# zigduino-v6d.net
KiCad netlist of a schematic drawn in EAGLE
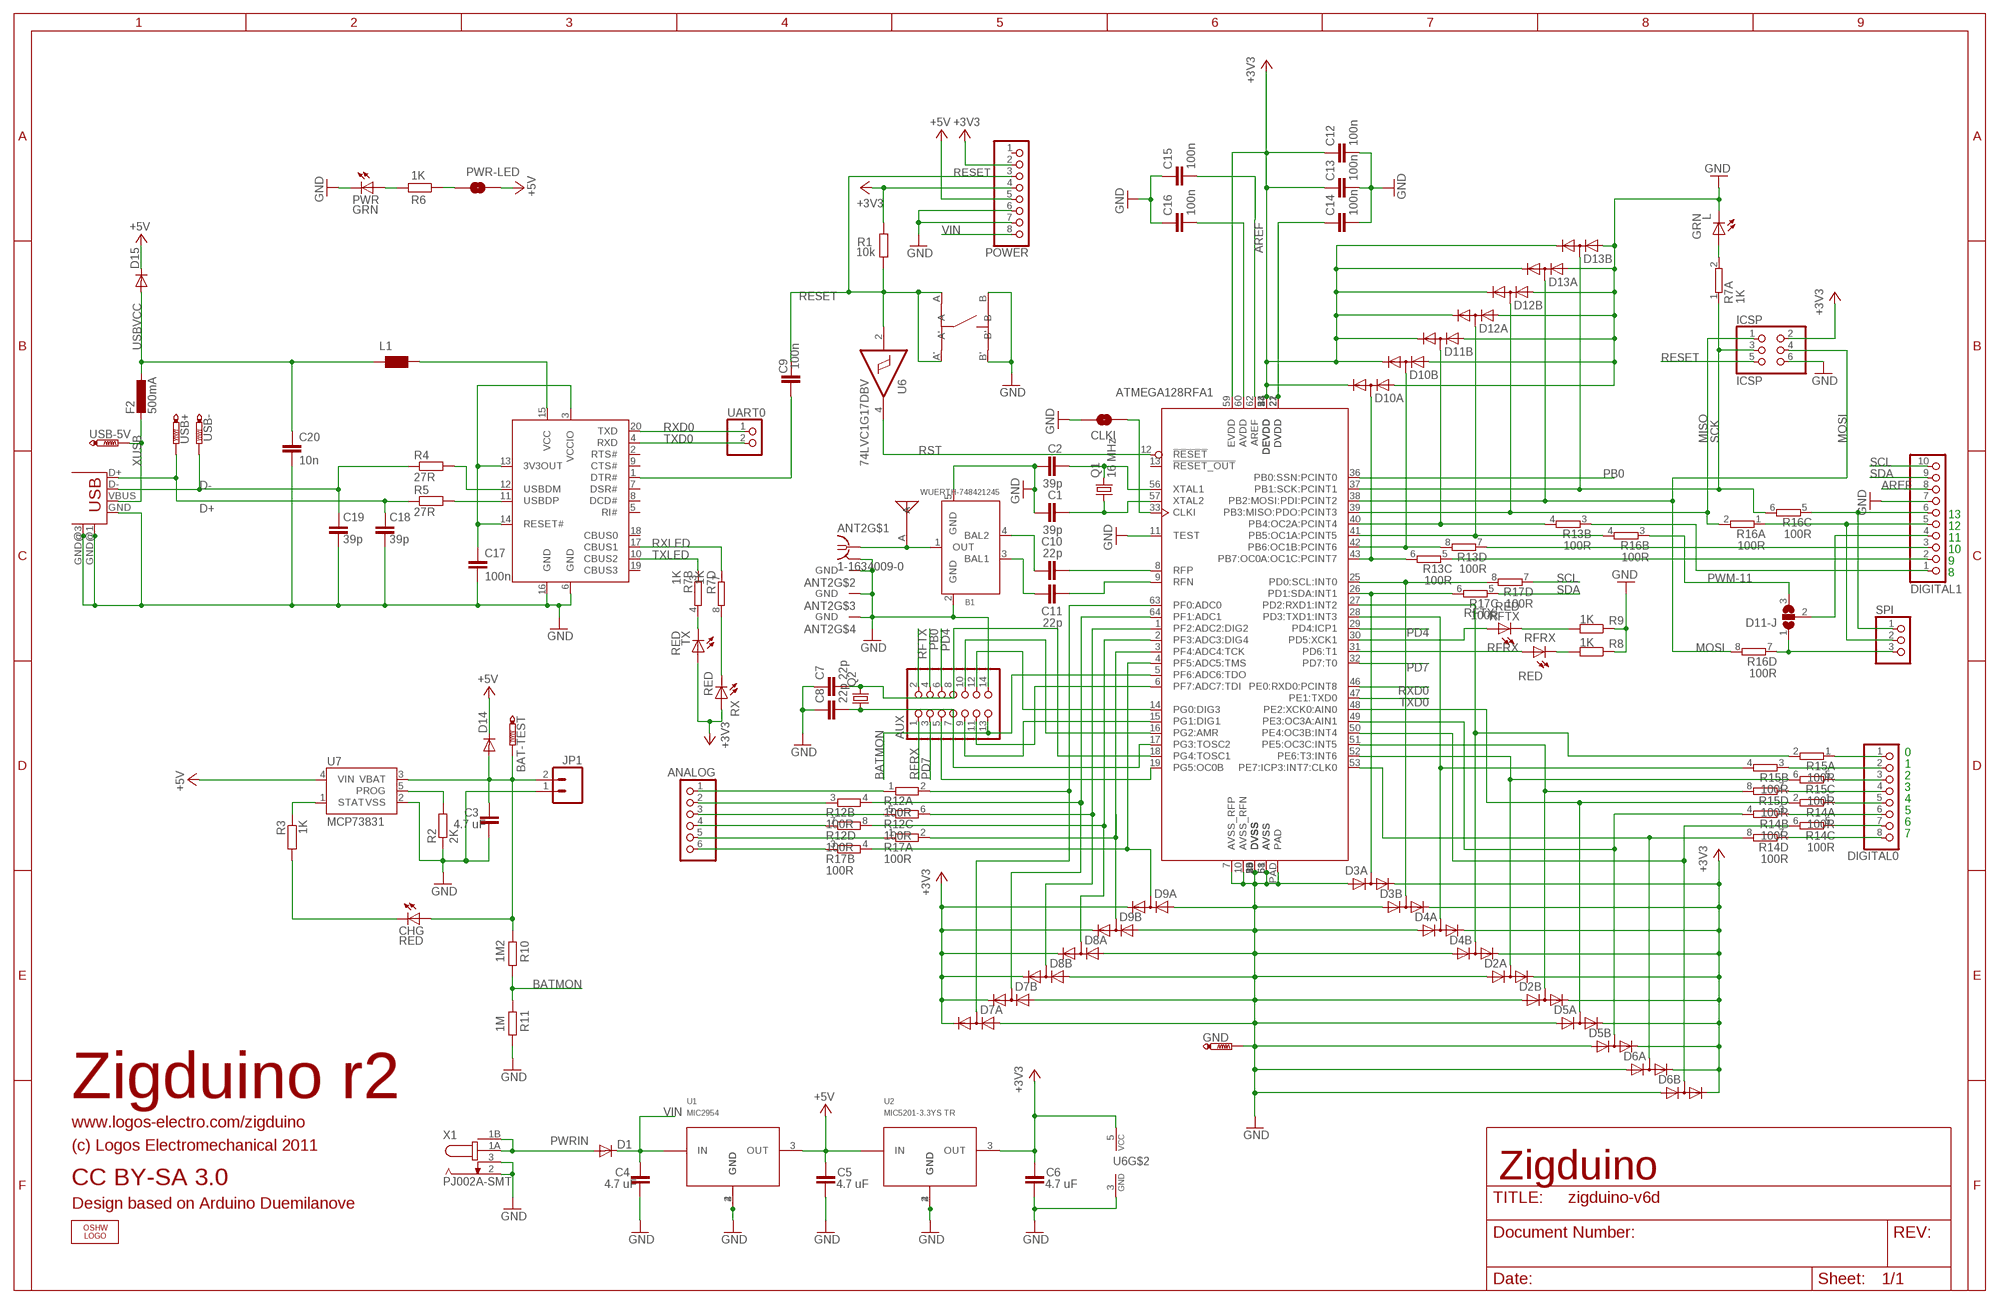
[diagram p0: schematic, sheet 1]

(export (version "E")
  (design (tool "Eeschema 10.0.6"))
  (components
    (comp (ref "ANALOG")
      (value "PINHD-1X6")
      (footprint "eagle-import:1X06")
      (fields (field (name "PARTNO") "19742"))
      (libsource (lib "eagle-import") (part "PINHD-1X6"))
    )
    (comp (ref "ANT1")
      (value "MOLEX-ANT")
      (footprint "eagle-import:MOLEX-ANT")
      (fields (field (name "PARTNO") "0479480001"))
      (libsource (lib "eagle-import") (part "MOLEX-ANT"))
    )
    (comp (ref "ANT2")
      (value "1-1634009-0")
      (footprint "eagle-import:MMCX-THRU")
      (fields (field (name "BOM") "EXCLUDE") (field (name "DNP") "T"))
      (libsource (lib "eagle-import") (part "1-1634009-0"))
    )
    (comp (ref "AUX")
      (value "PINHD-2X7_2.00")
      (footprint "eagle-import:2X07M")
      (fields (field (name "PARTNO") "00217"))
      (libsource (lib "eagle-import") (part "PINHD-2X7_2.00"))
    )
    (comp (ref "B1")
      (value "WUERTH-748421245")
      (footprint "eagle-import:WURTH-BALUN")
      (fields (field (name "PARTNO") "748421245"))
      (libsource (lib "eagle-import") (part "WUERTH-748421245"))
    )
    (comp (ref "BAT-TEST")
      (value "PTR1TP13SQ")
      (footprint "eagle-import:TP13SQ")
      (fields (field (name "PARTNO") "TP13"))
      (libsource (lib "eagle-import") (part "PTR1TP13SQ"))
    )
    (comp (ref "C1")
      (value "39p")
      (footprint "eagle-import:C0603")
      (fields (field (name "PARTNO") "C1608C0G1H390J"))
      (libsource (lib "eagle-import") (part "C-EUC0603"))
    )
    (comp (ref "C2")
      (value "39p")
      (footprint "eagle-import:C0603")
      (fields (field (name "PARTNO") "C1608C0G1H390J"))
      (libsource (lib "eagle-import") (part "C-EUC0603"))
    )
    (comp (ref "C3")
      (value "4.7 uF")
      (footprint "eagle-import:C1206")
      (fields (field (name "PARTNO") "C3216Y5V1H475Z"))
      (libsource (lib "eagle-import") (part "C-EUC1206"))
    )
    (comp (ref "C4")
      (value "4.7 uF")
      (footprint "eagle-import:C1206")
      (fields (field (name "PARTNO") "C3216Y5V1H475Z"))
      (libsource (lib "eagle-import") (part "C-EUC1206"))
    )
    (comp (ref "C5")
      (value "4.7 uF")
      (footprint "eagle-import:C1206")
      (fields (field (name "PARTNO") "C3216Y5V1H475Z"))
      (libsource (lib "eagle-import") (part "C-EUC1206"))
    )
    (comp (ref "C6")
      (value "4.7 uF")
      (footprint "eagle-import:C1206")
      (fields (field (name "PARTNO") "C3216Y5V1H475Z"))
      (libsource (lib "eagle-import") (part "C-EUC1206"))
    )
    (comp (ref "C7")
      (value "22p")
      (footprint "eagle-import:C0603")
      (fields (field (name "PARTNO") "GQM1885C1H220JB01D"))
      (libsource (lib "eagle-import") (part "C-EUC0603"))
    )
    (comp (ref "C8")
      (value "22p")
      (footprint "eagle-import:C0603")
      (fields (field (name "PARTNO") "GQM1885C1H220JB01D"))
      (libsource (lib "eagle-import") (part "C-EUC0603"))
    )
    (comp (ref "C9")
      (value "100n")
      (footprint "eagle-import:C0603")
      (fields (field (name "PARTNO") "CC0603MRY5V9BB104"))
      (libsource (lib "eagle-import") (part "C-EUC0603"))
    )
    (comp (ref "C10")
      (value "22p")
      (footprint "eagle-import:C0603")
      (fields (field (name "PARTNO") "GQM1885C1H220JB01D"))
      (libsource (lib "eagle-import") (part "C-EUC0603"))
    )
    (comp (ref "C11")
      (value "22p")
      (footprint "eagle-import:C0603")
      (fields (field (name "PARTNO") "GQM1885C1H220JB01D"))
      (libsource (lib "eagle-import") (part "C-EUC0603"))
    )
    (comp (ref "C12")
      (value "100n")
      (footprint "eagle-import:C0603")
      (fields (field (name "PARTNO") "CC0603MRY5V9BB104"))
      (libsource (lib "eagle-import") (part "C-EUC0603"))
    )
    (comp (ref "C13")
      (value "100n")
      (footprint "eagle-import:C0603")
      (fields (field (name "PARTNO") "CC0603MRY5V9BB104"))
      (libsource (lib "eagle-import") (part "C-EUC0603"))
    )
    (comp (ref "C14")
      (value "100n")
      (footprint "eagle-import:C0603")
      (fields (field (name "PARTNO") "CC0603MRY5V9BB104"))
      (libsource (lib "eagle-import") (part "C-EUC0603"))
    )
    (comp (ref "C15")
      (value "100n")
      (footprint "eagle-import:C0603")
      (fields (field (name "PARTNO") "CC0603MRY5V9BB104"))
      (libsource (lib "eagle-import") (part "C-EUC0603"))
    )
    (comp (ref "C16")
      (value "100n")
      (footprint "eagle-import:C0603")
      (fields (field (name "PARTNO") "CC0603MRY5V9BB104"))
      (libsource (lib "eagle-import") (part "C-EUC0603"))
    )
    (comp (ref "C17")
      (value "100n")
      (footprint "eagle-import:C0603")
      (fields (field (name "PARTNO") "CC0603MRY5V9BB104"))
      (libsource (lib "eagle-import") (part "C-EUC0603"))
    )
    (comp (ref "C18")
      (value "39p")
      (footprint "eagle-import:C0603")
      (fields (field (name "PARTNO") "C1608C0G1H390J"))
      (libsource (lib "eagle-import") (part "C-EUC0603"))
    )
    (comp (ref "C19")
      (value "39p")
      (footprint "eagle-import:C0603")
      (fields (field (name "PARTNO") "C1608C0G1H390J"))
      (libsource (lib "eagle-import") (part "C-EUC0603"))
    )
    (comp (ref "C20")
      (value "10n")
      (footprint "eagle-import:C0603")
      (fields (field (name "PARTNO") "GRM188R71H103KA01D"))
      (libsource (lib "eagle-import") (part "C-EUC0603"))
    )
    (comp (ref "CHG")
      (value "RED")
      (footprint "eagle-import:CHIP-LED0603")
      (fields (field (name "PARTNO") "LTST-C193KRKT-5A"))
      (libsource (lib "eagle-import") (part "LEDCHIP-LED0603"))
    )
    (comp (ref "CLKI")
      (value "SOLDERJUMPERTRACE")
      (footprint "eagle-import:SJ_2S-TRACE")
      (libsource (lib "eagle-import") (part "SOLDERJUMPERTRACE"))
    )
    (comp (ref "D1")
      (value "DIODE-SMB")
      (footprint "eagle-import:SMB")
      (fields (field (name "PARTNO") "B150B-13-F"))
      (libsource (lib "eagle-import") (part "DIODE-SMB"))
    )
    (comp (ref "D2")
      (value "SD103ASDM")
      (footprint "eagle-import:SOT26")
      (fields
        (field (name "BOM") "INCLUDE")
        (field (name "PARTNO") "SD103ASDM-7")
        (field (name "VOLT") "40V")
      )
      (libsource (lib "eagle-import") (part "SD103ASDM"))
    )
    (comp (ref "D3")
      (value "SD103ASDM")
      (footprint "eagle-import:SOT26")
      (fields
        (field (name "PARTNO") "SD103ASDM-7")
        (field (name "BOM") "INCLUDE")
        (field (name "VOLT") "40V")
      )
      (libsource (lib "eagle-import") (part "SD103ASDM"))
    )
    (comp (ref "D4")
      (value "SD103ASDM")
      (footprint "eagle-import:SOT26")
      (fields
        (field (name "PARTNO") "SD103ASDM-7")
        (field (name "VOLT") "40V")
        (field (name "BOM") "INCLUDE")
      )
      (libsource (lib "eagle-import") (part "SD103ASDM"))
    )
    (comp (ref "D5")
      (value "SD103ASDM")
      (footprint "eagle-import:SOT26")
      (fields
        (field (name "PARTNO") "SD103ASDM-7")
        (field (name "VOLT") "40V")
        (field (name "BOM") "INCLUDE")
      )
      (libsource (lib "eagle-import") (part "SD103ASDM"))
    )
    (comp (ref "D6")
      (value "SD103ASDM")
      (footprint "eagle-import:SOT26")
      (fields
        (field (name "PARTNO") "SD103ASDM-7")
        (field (name "VOLT") "40V")
        (field (name "BOM") "INCLUDE")
      )
      (libsource (lib "eagle-import") (part "SD103ASDM"))
    )
    (comp (ref "D7")
      (value "SD103ASDM")
      (footprint "eagle-import:SOT26")
      (fields
        (field (name "BOM") "INCLUDE")
        (field (name "PARTNO") "SD103ASDM-7")
        (field (name "VOLT") "40V")
      )
      (libsource (lib "eagle-import") (part "SD103ASDM"))
    )
    (comp (ref "D8")
      (value "SD103ASDM")
      (footprint "eagle-import:SOT26")
      (fields
        (field (name "PARTNO") "SD103ASDM-7")
        (field (name "BOM") "INCLUDE")
        (field (name "VOLT") "40V")
      )
      (libsource (lib "eagle-import") (part "SD103ASDM"))
    )
    (comp (ref "D9")
      (value "SD103ASDM")
      (footprint "eagle-import:SOT26")
      (fields
        (field (name "PARTNO") "SD103ASDM-7")
        (field (name "BOM") "INCLUDE")
        (field (name "VOLT") "40V")
      )
      (libsource (lib "eagle-import") (part "SD103ASDM"))
    )
    (comp (ref "D10")
      (value "SD103ASDM")
      (footprint "eagle-import:SOT26")
      (fields
        (field (name "BOM") "INCLUDE")
        (field (name "PARTNO") "SD103ASDM-7")
        (field (name "VOLT") "40V")
      )
      (libsource (lib "eagle-import") (part "SD103ASDM"))
    )
    (comp (ref "D11")
      (value "SD103ASDM")
      (footprint "eagle-import:SOT26")
      (fields (field (name "PARTNO") "SD103ASDM-7"))
      (libsource (lib "eagle-import") (part "SD103ASDM"))
    )
    (comp (ref "D11-J")
      (value "SJ2W")
      (footprint "eagle-import:SJ_2")
      (fields (field (name "PARTNO") "SJ3"))
      (libsource (lib "eagle-import") (part "SJ2W"))
    )
    (comp (ref "D12")
      (value "SD103ASDM")
      (footprint "eagle-import:SOT26")
      (fields
        (field (name "PARTNO") "SD103ASDM-7")
        (field (name "VOLT") "40V")
        (field (name "BOM") "INCLUDE")
      )
      (libsource (lib "eagle-import") (part "SD103ASDM"))
    )
    (comp (ref "D13")
      (value "SD103ASDM")
      (footprint "eagle-import:SOT26")
      (fields
        (field (name "BOM") "INCLUDE")
        (field (name "PARTNO") "SD103ASDM-7")
        (field (name "VOLT") "40V")
      )
      (libsource (lib "eagle-import") (part "SD103ASDM"))
    )
    (comp (ref "D14")
      (value "DIODE-SMB")
      (footprint "eagle-import:SMB")
      (fields (field (name "PARTNO") "B150B-13-F"))
      (libsource (lib "eagle-import") (part "DIODE-SMB"))
    )
    (comp (ref "D15")
      (value "DIODE-SMB")
      (footprint "eagle-import:SMB")
      (fields (field (name "PARTNO") "B150B-13-F"))
      (libsource (lib "eagle-import") (part "DIODE-SMB"))
    )
    (comp (ref "DIGITAL0")
      (value "PINHD-1X8")
      (footprint "eagle-import:1X08")
      (fields (field (name "PARTNO") "19743"))
      (libsource (lib "eagle-import") (part "PINHD-1X8"))
    )
    (comp (ref "DIGITAL1")
      (value "PINHD-1X10")
      (footprint "eagle-import:1X10")
      (fields (field (name "PARTNO") "20083"))
      (libsource (lib "eagle-import") (part "PINHD-1X10"))
    )
    (comp (ref "F2")
      (value "500mA")
      (footprint "eagle-import:L1812")
      (fields (field (name "PARTNO") "MF-MSMF050-2"))
      (libsource (lib "eagle-import") (part "L-EUL1812"))
    )
    (comp (ref "GND")
      (value "PTR1TP13SQ")
      (footprint "eagle-import:TP13SQ")
      (fields (field (name "PARTNO") "TP13"))
      (libsource (lib "eagle-import") (part "PTR1TP13SQ"))
    )
    (comp (ref "ICSP")
      (value "ICSP")
      (footprint "eagle-import:2X03")
      (fields (field (name "PARTNO") "961206-6404-AR"))
      (libsource (lib "eagle-import") (part "PINHD-2X3"))
    )
    (comp (ref "JP1")
      (value "M02-JST-2MM-SMT")
      (footprint "eagle-import:S2B-PH")
      (fields (field (name "PARTNO") "S2B-PH-SM4-TB(LF)(SN)"))
      (libsource (lib "eagle-import") (part "M02-JST-2MM-SMT"))
    )
    (comp (ref "L")
      (value "GRN")
      (footprint "eagle-import:CHIP-LED0603")
      (fields (field (name "PARTNO") "LTST-C193KGKT-5A"))
      (libsource (lib "eagle-import") (part "LEDCHIP-LED0603"))
    )
    (comp (ref "L1")
      (value "WE-CBF_0805")
      (footprint "eagle-import:0805")
      (fields (field (name "PARTNO") "MI0805K400R-10"))
      (libsource (lib "eagle-import") (part "WE-CBF_0805"))
    )
    (comp (ref "LOGO1")
      (value "OSHW_LOGO_FILLX0200-NT")
      (footprint "eagle-import:OSHW_FILLX200_NOTEXT")
      (libsource (lib "eagle-import") (part "OSHW_LOGO_FILLX0200-NT"))
    )
    (comp (ref "POWER")
      (value "PINHD-1X8")
      (footprint "eagle-import:1X08")
      (fields (field (name "PARTNO") "19743"))
      (libsource (lib "eagle-import") (part "PINHD-1X8"))
    )
    (comp (ref "PWR")
      (value "GRN")
      (footprint "eagle-import:CHIP-LED0603")
      (fields (field (name "PARTNO") "LTST-C193KGKT-5A"))
      (libsource (lib "eagle-import") (part "LEDCHIP-LED0603"))
    )
    (comp (ref "PWR-LED")
      (value "SOLDERJUMPERTRACE")
      (footprint "eagle-import:SJ_2S-TRACE")
      (libsource (lib "eagle-import") (part "SOLDERJUMPERTRACE"))
    )
    (comp (ref "Q1")
      (value "16 MHz")
      (footprint "eagle-import:CSM-3X")
      (fields (field (name "PARTNO") "ECS-160-20-3X-TR"))
      (libsource (lib "eagle-import") (part "CRYSTALCSM-3X"))
    )
    (comp (ref "Q2")
      (value "CRYSTALTC26H")
      (footprint "eagle-import:TC26H")
      (libsource (lib "eagle-import") (part "CRYSTALTC26H"))
    )
    (comp (ref "R1")
      (value "10k")
      (footprint "eagle-import:R0603")
      (fields (field (name "PARTNO") "RMCF0603FT10K0"))
      (libsource (lib "eagle-import") (part "R-EU_R0603"))
    )
    (comp (ref "R2")
      (value "2K")
      (footprint "eagle-import:R0603")
      (fields (field (name "PARTNO") "RC0603FR-072KL"))
      (libsource (lib "eagle-import") (part "R-EU_R0603"))
    )
    (comp (ref "R3")
      (value "1K")
      (footprint "eagle-import:R0603")
      (fields (field (name "PARTNO") "RMCF0603FT1K00"))
      (libsource (lib "eagle-import") (part "R-EU_R0603"))
    )
    (comp (ref "R4")
      (value "27R")
      (footprint "eagle-import:R0603")
      (fields (field (name "PARTNO") "RC0603JR-0727RL"))
      (libsource (lib "eagle-import") (part "R-EU_R0603"))
    )
    (comp (ref "R5")
      (value "27R")
      (footprint "eagle-import:R0603")
      (fields (field (name "PARTNO") "RC0603JR-0727RL"))
      (libsource (lib "eagle-import") (part "R-EU_R0603"))
    )
    (comp (ref "R6")
      (value "1K")
      (footprint "eagle-import:R0603")
      (fields (field (name "PARTNO") "RMCF0603FT1K00"))
      (libsource (lib "eagle-import") (part "R-EU_R0603"))
    )
    (comp (ref "R7")
      (value "1K")
      (footprint "eagle-import:CTS742C083-RES")
      (fields (field (name "BOM") "INCLUDE") (field (name "PARTNO") "742C083102JPTR"))
      (libsource (lib "eagle-import") (part "4R-NCTS742C083"))
    )
    (comp (ref "R8")
      (value "1K")
      (footprint "eagle-import:R0603")
      (fields (field (name "PARTNO") "RMCF0603FT1K00"))
      (libsource (lib "eagle-import") (part "R-EU_R0603"))
    )
    (comp (ref "R9")
      (value "1K")
      (footprint "eagle-import:R0603")
      (fields (field (name "PARTNO") "RMCF0603FT1K00"))
      (libsource (lib "eagle-import") (part "R-EU_R0603"))
    )
    (comp (ref "R10")
      (value "1M2")
      (footprint "eagle-import:R0603")
      (fields (field (name "PARTNO") "ERJ-3EKF1204V"))
      (libsource (lib "eagle-import") (part "R-EU_R0603"))
    )
    (comp (ref "R11")
      (value "1M")
      (footprint "eagle-import:R0603")
      (fields (field (name "PARTNO") "ERJ-3EKF1004V"))
      (libsource (lib "eagle-import") (part "R-EU_R0603"))
    )
    (comp (ref "R12")
      (value "100R")
      (footprint "eagle-import:CTS742C083-RES")
      (fields (field (name "PARTNO") "742C083101JPTR") (field (name "BOM") "INCLUDE"))
      (libsource (lib "eagle-import") (part "4R-NCTS742C083"))
    )
    (comp (ref "R13")
      (value "100R")
      (footprint "eagle-import:CTS742C083-RES")
      (fields (field (name "BOM") "INCLUDE") (field (name "PARTNO") "742C083101JPTR"))
      (libsource (lib "eagle-import") (part "4R-NCTS742C083"))
    )
    (comp (ref "R14")
      (value "100R")
      (footprint "eagle-import:CTS742C083-RES")
      (fields (field (name "BOM") "INCLUDE") (field (name "PARTNO") "742C083101JPTR"))
      (libsource (lib "eagle-import") (part "4R-NCTS742C083"))
    )
    (comp (ref "R15")
      (value "100R")
      (footprint "eagle-import:CTS742C083-RES")
      (fields (field (name "PARTNO") "742C083101JPTR") (field (name "BOM") "INCLUDE"))
      (libsource (lib "eagle-import") (part "4R-NCTS742C083"))
    )
    (comp (ref "R16")
      (value "100R")
      (footprint "eagle-import:CTS742C083-RES")
      (fields (field (name "BOM") "INCLUDE") (field (name "PARTNO") "742C083101JPTR"))
      (libsource (lib "eagle-import") (part "4R-NCTS742C083"))
    )
    (comp (ref "R17")
      (value "100R")
      (footprint "eagle-import:CTS742C083-RES")
      (fields (field (name "PARTNO") "742C083101JPTR") (field (name "BOM") "INCLUDE"))
      (libsource (lib "eagle-import") (part "4R-NCTS742C083"))
    )
    (comp (ref "RFRX")
      (value "RED")
      (footprint "eagle-import:CHIP-LED0603")
      (fields (field (name "PARTNO") "LTST-C193KRKT-5A"))
      (libsource (lib "eagle-import") (part "LEDCHIP-LED0603"))
    )
    (comp (ref "RFTX")
      (value "RED")
      (footprint "eagle-import:CHIP-LED0603")
      (fields (field (name "PARTNO") "LTST-C193KRKT-5A"))
      (libsource (lib "eagle-import") (part "LEDCHIP-LED0603"))
    )
    (comp (ref "RX")
      (value "RED")
      (footprint "eagle-import:CHIP-LED0603")
      (fields (field (name "PARTNO") "LTST-C193KRKT-5A"))
      (libsource (lib "eagle-import") (part "LEDCHIP-LED0603"))
    )
    (comp (ref "SPI")
      (value "PINHD-1X3")
      (footprint "eagle-import:1X03")
      (fields (field (name "PARTNO") "20152"))
      (libsource (lib "eagle-import") (part "PINHD-1X3"))
    )
    (comp (ref "SW1")
      (value "EVQ-PSD02K")
      (footprint "eagle-import:EVQPSD02K")
      (libsource (lib "eagle-import") (part "EVQ-PSD02K"))
    )
    (comp (ref "TX")
      (value "RED")
      (footprint "eagle-import:CHIP-LED0603")
      (fields (field (name "PARTNO") "LTST-C193KRKT-5A"))
      (libsource (lib "eagle-import") (part "LEDCHIP-LED0603"))
    )
    (comp (ref "U1")
      (value "MIC2954")
      (footprint "eagle-import:SOT223")
      (fields (field (name "PARTNO") "MIC2954-03WS-TR"))
      (libsource (lib "eagle-import") (part "MIC2954"))
    )
    (comp (ref "U2")
      (value "MIC5201-3.3YS TR")
      (footprint "eagle-import:SOT223")
      (libsource (lib "eagle-import") (part "MIC5201-3.3BS"))
    )
    (comp (ref "U3")
      (value "ATMEGA128RFA1")
      (footprint "eagle-import:QFN64")
      (fields (field (name "PARTNO") "ATMEGA128RFA1-ZUR"))
      (libsource (lib "eagle-import") (part "ATMEGA128RFA1"))
    )
    (comp (ref "U4")
      (value "FT231XS-R")
      (footprint "eagle-import:SSOP20")
      (libsource (lib "eagle-import") (part "FT231XS-R"))
    )
    (comp (ref "U6")
      (value "74LVC1G17DBV")
      (footprint "eagle-import:SOT23-5")
      (fields (field (name "BOM") "INCLUDE") (field (name "PARTNO") "SN74LVC1G17DBVR"))
      (libsource (lib "eagle-import") (part "741G17DBVLVC"))
    )
    (comp (ref "U7")
      (value "MCP73831")
      (footprint "eagle-import:SOT23-5")
      (fields (field (name "PARTNO") "MCP73831T-2ACI/OT"))
      (libsource (lib "eagle-import") (part "MCP73831"))
    )
    (comp (ref "UART0")
      (value "PINHD-1X2")
      (footprint "eagle-import:1X02")
      (fields (field (name "PARTNO") "00522"))
      (libsource (lib "eagle-import") (part "PINHD-1X2"))
    )
    (comp (ref "USB")
      (value "USB-MB-S")
      (footprint "eagle-import:USB-MB-S")
      (fields (field (name "PARTNO") "20236"))
      (libsource (lib "eagle-import") (part "USB-MB-S"))
    )
    (comp (ref "USB+")
      (value "PTR1TP13SQ")
      (footprint "eagle-import:TP13SQ")
      (fields (field (name "PARTNO") "TP13"))
      (libsource (lib "eagle-import") (part "PTR1TP13SQ"))
    )
    (comp (ref "USB-")
      (value "PTR1TP13SQ")
      (footprint "eagle-import:TP13SQ")
      (fields (field (name "PARTNO") "TP13"))
      (libsource (lib "eagle-import") (part "PTR1TP13SQ"))
    )
    (comp (ref "USB-5V")
      (value "PTR1TP13SQ")
      (footprint "eagle-import:TP13SQ")
      (fields (field (name "PARTNO") "TP13"))
      (libsource (lib "eagle-import") (part "PTR1TP13SQ"))
    )
    (comp (ref "X1")
      (value "PJ002A-SMT")
      (footprint "eagle-import:PJ002A-SMT")
      (fields (field (name "PARTNO") "PJ-002AH-SMT"))
      (libsource (lib "eagle-import") (part "PJ002A-SMT"))
    )
  )
  (nets
    (net (code "1") (name "+3V3") (class "Default")
      (node (ref "C12") (pin "1") (pinfunction "1_1") (pintype "passive"))
      (node (ref "C13") (pin "1") (pinfunction "1_1") (pintype "passive"))
      (node (ref "C6") (pin "1") (pinfunction "1_1") (pintype "passive"))
      (node (ref "D10") (pin "2") (pinfunction "C_2") (pintype "passive"))
      (node (ref "D10") (pin "5") (pinfunction "C_5") (pintype "passive"))
      (node (ref "D11") (pin "5") (pinfunction "C_5") (pintype "passive"))
      (node (ref "D12") (pin "2") (pinfunction "C_2") (pintype "passive"))
      (node (ref "D12") (pin "5") (pinfunction "C_5") (pintype "passive"))
      (node (ref "D13") (pin "2") (pinfunction "C_2") (pintype "passive"))
      (node (ref "D13") (pin "5") (pinfunction "C_5") (pintype "passive"))
      (node (ref "D2") (pin "2") (pinfunction "C_2") (pintype "passive"))
      (node (ref "D2") (pin "5") (pinfunction "C_5") (pintype "passive"))
      (node (ref "D3") (pin "2") (pinfunction "C_2") (pintype "passive"))
      (node (ref "D3") (pin "5") (pinfunction "C_5") (pintype "passive"))
      (node (ref "D4") (pin "2") (pinfunction "C_2") (pintype "passive"))
      (node (ref "D4") (pin "5") (pinfunction "C_5") (pintype "passive"))
      (node (ref "D5") (pin "2") (pinfunction "C_2") (pintype "passive"))
      (node (ref "D5") (pin "5") (pinfunction "C_5") (pintype "passive"))
      (node (ref "D6") (pin "2") (pinfunction "C_2") (pintype "passive"))
      (node (ref "D6") (pin "5") (pinfunction "C_5") (pintype "passive"))
      (node (ref "D7") (pin "2") (pinfunction "C_2") (pintype "passive"))
      (node (ref "D7") (pin "5") (pinfunction "C_5") (pintype "passive"))
      (node (ref "D8") (pin "2") (pinfunction "C_2") (pintype "passive"))
      (node (ref "D8") (pin "5") (pinfunction "C_5") (pintype "passive"))
      (node (ref "D9") (pin "2") (pinfunction "C_2") (pintype "passive"))
      (node (ref "D9") (pin "5") (pinfunction "C_5") (pintype "passive"))
      (node (ref "ICSP") (pin "2") (pinfunction "2_2") (pintype "passive"))
      (node (ref "POWER") (pin "2") (pinfunction "2_2") (pintype "passive"))
      (node (ref "POWER") (pin "4") (pinfunction "4_4") (pintype "passive"))
      (node (ref "R1") (pin "2") (pinfunction "2_2") (pintype "passive"))
      (node (ref "RX") (pin "A") (pinfunction "A_A") (pintype "passive"))
      (node (ref "TX") (pin "A") (pinfunction "A_A") (pintype "passive"))
      (node (ref "U2") (pin "3") (pinfunction "OUT_3") (pintype "bidirectional"))
      (node (ref "U3") (pin "23") (pinfunction "DEVDD_23") (pintype "bidirectional"))
      (node (ref "U3") (pin "34") (pinfunction "DEVDD_34") (pintype "bidirectional"))
      (node (ref "U3") (pin "44") (pinfunction "DEVDD_44") (pintype "bidirectional"))
      (node (ref "U3") (pin "54") (pinfunction "DEVDD_54") (pintype "bidirectional"))
      (node (ref "U3") (pin "59") (pinfunction "EVDD_59") (pintype "bidirectional"))
      (node (ref "U6") (pin "5") (pinfunction "VCC_5") (pintype "power_in"))
    )
    (net (code "2") (name "+5V") (class "Default")
      (node (ref "C5") (pin "1") (pinfunction "1_1") (pintype "passive"))
      (node (ref "D14") (pin "C") (pinfunction "C_C") (pintype "passive"))
      (node (ref "D15") (pin "C") (pinfunction "C_C") (pintype "passive"))
      (node (ref "POWER") (pin "5") (pinfunction "5_5") (pintype "passive"))
      (node (ref "PWR-LED") (pin "2") (pinfunction "2_2") (pintype "passive"))
      (node (ref "U1") (pin "3") (pinfunction "OUT_3") (pintype "bidirectional"))
      (node (ref "U2") (pin "1") (pinfunction "IN_1") (pintype "bidirectional"))
      (node (ref "U7") (pin "4") (pinfunction "VIN_4") (pintype "power_in"))
    )
    (net (code "3") (name "/AREF") (class "Default")
      (node (ref "C15") (pin "2") (pinfunction "2_2") (pintype "passive"))
      (node (ref "DIGITAL1") (pin "8") (pinfunction "8_8") (pintype "passive"))
      (node (ref "U3") (pin "62") (pinfunction "AREF_62") (pintype "bidirectional"))
    )
    (net (code "4") (name "/BATMON") (class "Default")
      (node (ref "AUX") (pin "13") (pinfunction "13_13") (pintype "passive"))
      (node (ref "R10") (pin "2") (pinfunction "2_2") (pintype "passive"))
      (node (ref "R11") (pin "1") (pinfunction "1_1") (pintype "passive"))
      (node (ref "U3") (pin "5") (pinfunction "PF6:ADC6:TDO_5") (pintype "bidirectional"))
    )
    (net (code "5") (name "/D+") (class "Default")
      (node (ref "C18") (pin "1") (pinfunction "1_1") (pintype "passive"))
      (node (ref "R5") (pin "1") (pinfunction "1_1") (pintype "passive"))
      (node (ref "USB") (pin "D+") (pinfunction "D+_D+") (pintype "bidirectional"))
      (node (ref "USB+") (pin "TP") (pinfunction "TP_TP") (pintype "input"))
    )
    (net (code "6") (name "/D-") (class "Default")
      (node (ref "C19") (pin "1") (pinfunction "1_1") (pintype "passive"))
      (node (ref "R4") (pin "1") (pinfunction "1_1") (pintype "passive"))
      (node (ref "USB") (pin "D-") (pinfunction "D-_D-") (pintype "bidirectional"))
      (node (ref "USB-") (pin "TP") (pinfunction "TP_TP") (pintype "input"))
    )
    (net (code "7") (name "/MISO") (class "Default")
      (node (ref "D12") (pin "1") (pinfunction "AC_1") (pintype "passive"))
      (node (ref "ICSP") (pin "1") (pinfunction "1_1") (pintype "passive"))
      (node (ref "R16") (pin "2") (pinfunction "2_2") (pintype "passive"))
      (node (ref "U3") (pin "39") (pinfunction "PB3:MISO:PDO:PCINT3_39") (pintype "bidirectional"))
    )
    (net (code "8") (name "/MOSI") (class "Default")
      (node (ref "D13") (pin "4") (pinfunction "AC_4") (pintype "passive"))
      (node (ref "ICSP") (pin "4") (pinfunction "4_4") (pintype "passive"))
      (node (ref "R16") (pin "8") (pinfunction "2_8") (pintype "passive"))
      (node (ref "U3") (pin "38") (pinfunction "PB2:MOSI:PDI:PCINT2_38") (pintype "bidirectional"))
    )
    (net (code "9") (name "/PB0") (class "Default")
      (node (ref "AUX") (pin "4") (pinfunction "4_4") (pintype "passive"))
      (node (ref "U3") (pin "36") (pinfunction "PB0:SSN:PCINT0_36") (pintype "bidirectional"))
    )
    (net (code "10") (name "/PD4") (class "Default")
      (node (ref "AUX") (pin "6") (pinfunction "6_6") (pintype "passive"))
      (node (ref "U3") (pin "29") (pinfunction "PD4:ICP1_29") (pintype "bidirectional"))
    )
    (net (code "11") (name "/PD7") (class "Default")
      (node (ref "AUX") (pin "3") (pinfunction "3_3") (pintype "passive"))
      (node (ref "U3") (pin "32") (pinfunction "PD7:T0_32") (pintype "bidirectional"))
    )
    (net (code "12") (name "/PWM-11") (class "Default")
      (node (ref "D11-J") (pin "3") (pinfunction "3_3") (pintype "passive"))
      (node (ref "R16") (pin "3") (pinfunction "1_3") (pintype "passive"))
    )
    (net (code "13") (name "/PWRIN") (class "Default")
      (node (ref "D1") (pin "A") (pinfunction "A_A") (pintype "passive"))
      (node (ref "X1") (pin "1A") (pinfunction "1A_1A") (pintype "passive"))
      (node (ref "X1") (pin "1B") (pinfunction "1B_1B") (pintype "passive"))
    )
    (net (code "14") (name "/RESET") (class "Default")
      (node (ref "C9") (pin "2") (pinfunction "2_2") (pintype "passive"))
      (node (ref "ICSP") (pin "5") (pinfunction "5_5") (pintype "passive"))
      (node (ref "POWER") (pin "3") (pinfunction "3_3") (pintype "passive"))
      (node (ref "R1") (pin "1") (pinfunction "1_1") (pintype "passive"))
      (node (ref "SW1") (pin "A") (pinfunction "A_A") (pintype "bidirectional"))
      (node (ref "SW1") (pin "A'") (pinfunction "A'_A'") (pintype "bidirectional"))
      (node (ref "U6") (pin "2") (pinfunction "I_2") (pintype "input"))
    )
    (net (code "15") (name "/RFRX") (class "Default")
      (node (ref "AUX") (pin "1") (pinfunction "1_1") (pintype "passive"))
      (node (ref "RFRX") (pin "A") (pinfunction "A_A") (pintype "passive"))
      (node (ref "U3") (pin "31") (pinfunction "PD6:T1_31") (pintype "bidirectional"))
    )
    (net (code "16") (name "/RFTX") (class "Default")
      (node (ref "AUX") (pin "2") (pinfunction "2_2") (pintype "passive"))
      (node (ref "RFTX") (pin "A") (pinfunction "A_A") (pintype "passive"))
      (node (ref "U3") (pin "30") (pinfunction "PD5:XCK1_30") (pintype "bidirectional"))
    )
    (net (code "17") (name "/RST") (class "Default")
      (node (ref "U3") (pin "12") (pinfunction "~{RESET}_12") (pintype "bidirectional"))
      (node (ref "U6") (pin "4") (pinfunction "O_4") (pintype "output"))
    )
    (net (code "18") (name "/RXD0") (class "Default")
      (node (ref "U3") (pin "46") (pinfunction "PE0:RXD0:PCINT8_46") (pintype "bidirectional"))
      (node (ref "U4") (pin "20") (pinfunction "TXD_20") (pintype "bidirectional"))
      (node (ref "UART0") (pin "1") (pinfunction "1_1") (pintype "passive"))
    )
    (net (code "19") (name "/RXLED") (class "Default")
      (node (ref "R7") (pin "7") (pinfunction "1_7") (pintype "passive"))
      (node (ref "U4") (pin "17") (pinfunction "CBUS1_17") (pintype "bidirectional"))
    )
    (net (code "20") (name "/SCK") (class "Default")
      (node (ref "D13") (pin "1") (pinfunction "AC_1") (pintype "passive"))
      (node (ref "ICSP") (pin "3") (pinfunction "3_3") (pintype "passive"))
      (node (ref "R16") (pin "6") (pinfunction "2_6") (pintype "passive"))
      (node (ref "R7") (pin "1") (pinfunction "1_1") (pintype "passive"))
      (node (ref "U3") (pin "37") (pinfunction "PB1:SCK:PCINT1_37") (pintype "bidirectional"))
    )
    (net (code "21") (name "/SCL") (class "Default")
      (node (ref "DIGITAL1") (pin "10") (pinfunction "10_10") (pintype "passive"))
      (node (ref "R17") (pin "7") (pinfunction "1_7") (pintype "passive"))
    )
    (net (code "22") (name "/SDA") (class "Default")
      (node (ref "DIGITAL1") (pin "9") (pinfunction "9_9") (pintype "passive"))
      (node (ref "R17") (pin "5") (pinfunction "1_5") (pintype "passive"))
    )
    (net (code "23") (name "/TXD0") (class "Default")
      (node (ref "U3") (pin "47") (pinfunction "PE1:TXD0_47") (pintype "bidirectional"))
      (node (ref "U4") (pin "4") (pinfunction "RXD_4") (pintype "bidirectional"))
      (node (ref "UART0") (pin "2") (pinfunction "2_2") (pintype "passive"))
    )
    (net (code "24") (name "/TXLED") (class "Default")
      (node (ref "R7") (pin "3") (pinfunction "1_3") (pintype "passive"))
      (node (ref "U4") (pin "10") (pinfunction "CBUS2_10") (pintype "bidirectional"))
    )
    (net (code "25") (name "/USBVCC") (class "Default")
      (node (ref "C20") (pin "1") (pinfunction "1_1") (pintype "passive"))
      (node (ref "D15") (pin "A") (pinfunction "A_A") (pintype "passive"))
      (node (ref "F2") (pin "1") (pinfunction "1_1") (pintype "passive"))
      (node (ref "L1") (pin "1") (pinfunction "1_1") (pintype "passive"))
    )
    (net (code "26") (name "/VIN") (class "Default")
      (node (ref "C4") (pin "1") (pinfunction "1_1") (pintype "passive"))
      (node (ref "D1") (pin "C") (pinfunction "C_C") (pintype "passive"))
      (node (ref "POWER") (pin "8") (pinfunction "8_8") (pintype "passive"))
      (node (ref "U1") (pin "1") (pinfunction "IN_1") (pintype "bidirectional"))
    )
    (net (code "27") (name "/XUSB") (class "Default")
      (node (ref "F2") (pin "2") (pinfunction "2_2") (pintype "passive"))
      (node (ref "USB") (pin "VBUS") (pinfunction "VBUS_VBUS") (pintype "bidirectional"))
      (node (ref "USB-5V") (pin "TP") (pinfunction "TP_TP") (pintype "input"))
    )
    (net (code "28") (name "GND") (class "Default")
      (node (ref "ANT2") (pin "G@0") (pinfunction "GND_G@0") (pintype "power_in"))
      (node (ref "ANT2") (pin "G@1") (pinfunction "GND_G@1") (pintype "power_in"))
      (node (ref "ANT2") (pin "G@2") (pinfunction "GND_G@2") (pintype "power_in"))
      (node (ref "ANT2") (pin "G@3") (pinfunction "GND_G@3") (pintype "power_in"))
      (node (ref "AUX") (pin "14") (pinfunction "14_14") (pintype "passive"))
      (node (ref "B1") (pin "2") (pinfunction "GND_2") (pintype "bidirectional"))
      (node (ref "B1") (pin "5") (pinfunction "GND_5") (pintype "bidirectional"))
      (node (ref "C1") (pin "1") (pinfunction "1_1") (pintype "passive"))
      (node (ref "C12") (pin "2") (pinfunction "2_2") (pintype "passive"))
      (node (ref "C13") (pin "2") (pinfunction "2_2") (pintype "passive"))
      (node (ref "C14") (pin "2") (pinfunction "2_2") (pintype "passive"))
      (node (ref "C15") (pin "1") (pinfunction "1_1") (pintype "passive"))
      (node (ref "C16") (pin "1") (pinfunction "1_1") (pintype "passive"))
      (node (ref "C17") (pin "2") (pinfunction "2_2") (pintype "passive"))
      (node (ref "C18") (pin "2") (pinfunction "2_2") (pintype "passive"))
      (node (ref "C19") (pin "2") (pinfunction "2_2") (pintype "passive"))
      (node (ref "C2") (pin "1") (pinfunction "1_1") (pintype "passive"))
      (node (ref "C20") (pin "2") (pinfunction "2_2") (pintype "passive"))
      (node (ref "C3") (pin "2") (pinfunction "2_2") (pintype "passive"))
      (node (ref "C4") (pin "2") (pinfunction "2_2") (pintype "passive"))
      (node (ref "C5") (pin "2") (pinfunction "2_2") (pintype "passive"))
      (node (ref "C6") (pin "2") (pinfunction "2_2") (pintype "passive"))
      (node (ref "C7") (pin "1") (pinfunction "1_1") (pintype "passive"))
      (node (ref "C8") (pin "1") (pinfunction "1_1") (pintype "passive"))
      (node (ref "CLKI") (pin "2") (pinfunction "2_2") (pintype "passive"))
      (node (ref "D10") (pin "3") (pinfunction "A_3") (pintype "passive"))
      (node (ref "D10") (pin "6") (pinfunction "A_6") (pintype "passive"))
      (node (ref "D11") (pin "6") (pinfunction "A_6") (pintype "passive"))
      (node (ref "D12") (pin "3") (pinfunction "A_3") (pintype "passive"))
      (node (ref "D12") (pin "6") (pinfunction "A_6") (pintype "passive"))
      (node (ref "D13") (pin "3") (pinfunction "A_3") (pintype "passive"))
      (node (ref "D13") (pin "6") (pinfunction "A_6") (pintype "passive"))
      (node (ref "D2") (pin "3") (pinfunction "A_3") (pintype "passive"))
      (node (ref "D2") (pin "6") (pinfunction "A_6") (pintype "passive"))
      (node (ref "D3") (pin "3") (pinfunction "A_3") (pintype "passive"))
      (node (ref "D3") (pin "6") (pinfunction "A_6") (pintype "passive"))
      (node (ref "D4") (pin "3") (pinfunction "A_3") (pintype "passive"))
      (node (ref "D4") (pin "6") (pinfunction "A_6") (pintype "passive"))
      (node (ref "D5") (pin "3") (pinfunction "A_3") (pintype "passive"))
      (node (ref "D5") (pin "6") (pinfunction "A_6") (pintype "passive"))
      (node (ref "D6") (pin "3") (pinfunction "A_3") (pintype "passive"))
      (node (ref "D6") (pin "6") (pinfunction "A_6") (pintype "passive"))
      (node (ref "D7") (pin "3") (pinfunction "A_3") (pintype "passive"))
      (node (ref "D7") (pin "6") (pinfunction "A_6") (pintype "passive"))
      (node (ref "D8") (pin "3") (pinfunction "A_3") (pintype "passive"))
      (node (ref "D8") (pin "6") (pinfunction "A_6") (pintype "passive"))
      (node (ref "D9") (pin "3") (pinfunction "A_3") (pintype "passive"))
      (node (ref "D9") (pin "6") (pinfunction "A_6") (pintype "passive"))
      (node (ref "DIGITAL1") (pin "7") (pinfunction "7_7") (pintype "passive"))
      (node (ref "GND") (pin "TP") (pinfunction "TP_TP") (pintype "input"))
      (node (ref "ICSP") (pin "6") (pinfunction "6_6") (pintype "passive"))
      (node (ref "JP1") (pin "1") (pinfunction "1_1") (pintype "passive"))
      (node (ref "L") (pin "C") (pinfunction "C_C") (pintype "passive"))
      (node (ref "POWER") (pin "6") (pinfunction "6_6") (pintype "passive"))
      (node (ref "POWER") (pin "7") (pinfunction "7_7") (pintype "passive"))
      (node (ref "PWR") (pin "C") (pinfunction "C_C") (pintype "passive"))
      (node (ref "R11") (pin "2") (pinfunction "2_2") (pintype "passive"))
      (node (ref "R2") (pin "1") (pinfunction "1_1") (pintype "passive"))
      (node (ref "R8") (pin "1") (pinfunction "1_1") (pintype "passive"))
      (node (ref "R9") (pin "1") (pinfunction "1_1") (pintype "passive"))
      (node (ref "SW1") (pin "B") (pinfunction "B_B") (pintype "bidirectional"))
      (node (ref "SW1") (pin "B'") (pinfunction "B'_B'") (pintype "bidirectional"))
      (node (ref "U1") (pin "2") (pinfunction "GND_2") (pintype "bidirectional"))
      (node (ref "U1") (pin "4") (pinfunction "GND_4") (pintype "bidirectional"))
      (node (ref "U2") (pin "2") (pinfunction "GND_2") (pintype "bidirectional"))
      (node (ref "U2") (pin "4") (pinfunction "GND_4") (pintype "bidirectional"))
      (node (ref "U3") (pin "10") (pinfunction "AVSS_RFN_10") (pintype "bidirectional"))
      (node (ref "U3") (pin "11") (pinfunction "TEST_11") (pintype "bidirectional"))
      (node (ref "U3") (pin "20") (pinfunction "DVSS_20") (pintype "bidirectional"))
      (node (ref "U3") (pin "24") (pinfunction "DVSS_24") (pintype "bidirectional"))
      (node (ref "U3") (pin "35") (pinfunction "DVSS_35") (pintype "bidirectional"))
      (node (ref "U3") (pin "45") (pinfunction "DVSS_45") (pintype "bidirectional"))
      (node (ref "U3") (pin "55") (pinfunction "DVSS_55") (pintype "bidirectional"))
      (node (ref "U3") (pin "58") (pinfunction "AVSS_58") (pintype "bidirectional"))
      (node (ref "U3") (pin "61") (pinfunction "AVSS_61") (pintype "bidirectional"))
      (node (ref "U3") (pin "7") (pinfunction "AVSS_RFP_7") (pintype "bidirectional"))
      (node (ref "U3") (pin "PAD") (pinfunction "PAD_PAD") (pintype "bidirectional"))
      (node (ref "U4") (pin "16") (pinfunction "GND_16") (pintype "bidirectional"))
      (node (ref "U4") (pin "6") (pinfunction "GND_6") (pintype "bidirectional"))
      (node (ref "U6") (pin "3") (pinfunction "GND_3") (pintype "power_in"))
      (node (ref "U7") (pin "2") (pinfunction "VSS_2") (pintype "power_in"))
      (node (ref "USB") (pin "GND") (pinfunction "GND_GND") (pintype "bidirectional"))
      (node (ref "USB") (pin "GND@1") (pinfunction "GND_GND@1") (pintype "bidirectional"))
      (node (ref "USB") (pin "GND@3") (pinfunction "GND_GND@3") (pintype "bidirectional"))
      (node (ref "X1") (pin "2") (pinfunction "2_2") (pintype "passive"))
      (node (ref "X1") (pin "3") (pinfunction "3_3") (pintype "passive"))
    )
    (net (code "29") (name "Net-(ANALOG-Pad1)") (class "Default")
      (node (ref "ANALOG") (pin "1") (pinfunction "1_1") (pintype "passive"))
      (node (ref "R12") (pin "1") (pinfunction "1_1") (pintype "passive"))
    )
    (net (code "30") (name "Net-(ANALOG-Pad5)") (class "Default")
      (node (ref "ANALOG") (pin "5") (pinfunction "5_5") (pintype "passive"))
      (node (ref "R17") (pin "1") (pinfunction "1_1") (pintype "passive"))
    )
    (net (code "31") (name "Net-(ANT2A-1)") (class "Default")
      (node (ref "ANT1") (pin "A") (pinfunction "A_A") (pintype "bidirectional"))
      (node (ref "ANT2") (pin "C") (pinfunction "1_C") (pintype "passive"))
      (node (ref "B1") (pin "1") (pinfunction "OUT_1") (pintype "bidirectional"))
    )
    (net (code "32") (name "Net-(B1-BAL1)") (class "Default")
      (node (ref "B1") (pin "3") (pinfunction "BAL1_3") (pintype "bidirectional"))
      (node (ref "C11") (pin "1") (pinfunction "1_1") (pintype "passive"))
    )
    (net (code "33") (name "Net-(B1-BAL2)") (class "Default")
      (node (ref "B1") (pin "4") (pinfunction "BAL2_4") (pintype "bidirectional"))
      (node (ref "C10") (pin "1") (pinfunction "1_1") (pintype "passive"))
    )
    (net (code "34") (name "Net-(C14-Pad1)") (class "Default")
      (node (ref "C14") (pin "1") (pinfunction "1_1") (pintype "passive"))
      (node (ref "U3") (pin "21") (pinfunction "DVDD_21") (pintype "bidirectional"))
      (node (ref "U3") (pin "22") (pinfunction "DVDD_22") (pintype "bidirectional"))
    )
    (net (code "35") (name "Net-(CHG-PadC)") (class "Default")
      (node (ref "CHG") (pin "C") (pinfunction "C_C") (pintype "passive"))
      (node (ref "R3") (pin "2") (pinfunction "2_2") (pintype "passive"))
    )
    (net (code "36") (name "Net-(D2A-AC)") (class "Default")
      (node (ref "D2") (pin "4") (pinfunction "AC_4") (pintype "passive"))
      (node (ref "R15") (pin "6") (pinfunction "2_6") (pintype "passive"))
      (node (ref "U3") (pin "52") (pinfunction "PE6:T3:INT6_52") (pintype "bidirectional"))
    )
    (net (code "37") (name "Net-(D2B-AC)") (class "Default")
      (node (ref "D2") (pin "1") (pinfunction "AC_1") (pintype "passive"))
      (node (ref "R15") (pin "8") (pinfunction "2_8") (pintype "passive"))
      (node (ref "U3") (pin "51") (pinfunction "PE5:OC3C:INT5_51") (pintype "bidirectional"))
    )
    (net (code "38") (name "Net-(D3A-AC)") (class "Default")
      (node (ref "D3") (pin "4") (pinfunction "AC_4") (pintype "passive"))
      (node (ref "R17") (pin "6") (pinfunction "2_6") (pintype "passive"))
      (node (ref "U3") (pin "26") (pinfunction "PD1:SDA:INT1_26") (pintype "bidirectional"))
    )
    (net (code "39") (name "Net-(D3B-AC)") (class "Default")
      (node (ref "D3") (pin "1") (pinfunction "AC_1") (pintype "passive"))
      (node (ref "R17") (pin "8") (pinfunction "2_8") (pintype "passive"))
      (node (ref "U3") (pin "25") (pinfunction "PD0:SCL:INT0_25") (pintype "bidirectional"))
    )
    (net (code "40") (name "Net-(D4A-AC)") (class "Default")
      (node (ref "D4") (pin "4") (pinfunction "AC_4") (pintype "passive"))
      (node (ref "R15") (pin "4") (pinfunction "2_4") (pintype "passive"))
      (node (ref "U3") (pin "28") (pinfunction "PD3:TXD1:INT3_28") (pintype "bidirectional"))
    )
    (net (code "41") (name "Net-(D4B-AC)") (class "Default")
      (node (ref "D4") (pin "1") (pinfunction "AC_1") (pintype "passive"))
      (node (ref "R15") (pin "2") (pinfunction "2_2") (pintype "passive"))
      (node (ref "U3") (pin "27") (pinfunction "PD2:RXD1:INT2_27") (pintype "bidirectional"))
    )
    (net (code "42") (name "Net-(D5A-AC)") (class "Default")
      (node (ref "D5") (pin "4") (pinfunction "AC_4") (pintype "passive"))
      (node (ref "R14") (pin "2") (pinfunction "2_2") (pintype "passive"))
      (node (ref "U3") (pin "48") (pinfunction "PE2:XCK0:AIN0_48") (pintype "bidirectional"))
    )
    (net (code "43") (name "Net-(D5B-AC)") (class "Default")
      (node (ref "D5") (pin "1") (pinfunction "AC_1") (pintype "passive"))
      (node (ref "R14") (pin "4") (pinfunction "2_4") (pintype "passive"))
      (node (ref "U3") (pin "49") (pinfunction "PE3:OC3A:AIN1_49") (pintype "bidirectional"))
    )
    (net (code "44") (name "Net-(D6A-AC)") (class "Default")
      (node (ref "D6") (pin "4") (pinfunction "AC_4") (pintype "passive"))
      (node (ref "R14") (pin "8") (pinfunction "2_8") (pintype "passive"))
      (node (ref "U3") (pin "53") (pinfunction "PE7:ICP3:INT7:CLK0_53") (pintype "bidirectional"))
    )
    (net (code "45") (name "Net-(D6B-AC)") (class "Default")
      (node (ref "D6") (pin "1") (pinfunction "AC_1") (pintype "passive"))
      (node (ref "R14") (pin "6") (pinfunction "2_6") (pintype "passive"))
      (node (ref "U3") (pin "50") (pinfunction "PE4:OC3B:INT4_50") (pintype "bidirectional"))
    )
    (net (code "46") (name "Net-(D7A-AC)") (class "Default")
      (node (ref "D7") (pin "4") (pinfunction "AC_4") (pintype "passive"))
      (node (ref "R12") (pin "2") (pinfunction "2_2") (pintype "passive"))
      (node (ref "U3") (pin "63") (pinfunction "PF0:ADC0_63") (pintype "bidirectional"))
    )
    (net (code "47") (name "Net-(D7B-AC)") (class "Default")
      (node (ref "D7") (pin "1") (pinfunction "AC_1") (pintype "passive"))
      (node (ref "R12") (pin "4") (pinfunction "2_4") (pintype "passive"))
      (node (ref "U3") (pin "64") (pinfunction "PF1:ADC1_64") (pintype "bidirectional"))
    )
    (net (code "48") (name "Net-(D8A-AC)") (class "Default")
      (node (ref "D8") (pin "4") (pinfunction "AC_4") (pintype "passive"))
      (node (ref "R12") (pin "8") (pinfunction "2_8") (pintype "passive"))
      (node (ref "U3") (pin "2") (pinfunction "PF3:ADC3:DIG4_2") (pintype "bidirectional"))
    )
    (net (code "49") (name "Net-(D8B-AC)") (class "Default")
      (node (ref "D8") (pin "1") (pinfunction "AC_1") (pintype "passive"))
      (node (ref "R12") (pin "6") (pinfunction "2_6") (pintype "passive"))
      (node (ref "U3") (pin "1") (pinfunction "PF2:ADC2:DIG2_1") (pintype "bidirectional"))
    )
    (net (code "50") (name "Net-(D9A-AC)") (class "Default")
      (node (ref "D9") (pin "4") (pinfunction "AC_4") (pintype "passive"))
      (node (ref "R17") (pin "4") (pinfunction "2_4") (pintype "passive"))
      (node (ref "U3") (pin "4") (pinfunction "PF5:ADC5:TMS_4") (pintype "bidirectional"))
    )
    (net (code "51") (name "Net-(D9B-AC)") (class "Default")
      (node (ref "D9") (pin "1") (pinfunction "AC_1") (pintype "passive"))
      (node (ref "R17") (pin "2") (pinfunction "2_2") (pintype "passive"))
      (node (ref "U3") (pin "3") (pinfunction "PF4:ADC4:TCK_3") (pintype "bidirectional"))
    )
    (net (code "52") (name "Net-(D10A-AC)") (class "Default")
      (node (ref "D10") (pin "4") (pinfunction "AC_4") (pintype "passive"))
      (node (ref "R13") (pin "6") (pinfunction "2_6") (pintype "passive"))
      (node (ref "U3") (pin "43") (pinfunction "PB7:OC0A:OC1C:PCINT7_43") (pintype "bidirectional"))
    )
    (net (code "53") (name "Net-(D10B-AC)") (class "Default")
      (node (ref "D10") (pin "1") (pinfunction "AC_1") (pintype "passive"))
      (node (ref "R13") (pin "8") (pinfunction "2_8") (pintype "passive"))
      (node (ref "U3") (pin "42") (pinfunction "PB6:OC1B:PCINT6_42") (pintype "bidirectional"))
    )
    (net (code "54") (name "Net-(D11-J-Pad2)") (class "Default")
      (node (ref "D11-J") (pin "2") (pinfunction "2_2") (pintype "passive"))
      (node (ref "DIGITAL1") (pin "4") (pinfunction "4_4") (pintype "passive"))
    )
    (net (code "55") (name "Net-(D11B-AC)") (class "Default")
      (node (ref "D11") (pin "1") (pinfunction "AC_1") (pintype "passive"))
      (node (ref "R13") (pin "4") (pinfunction "2_4") (pintype "passive"))
      (node (ref "U3") (pin "40") (pinfunction "PB4:OC2A:PCINT4_40") (pintype "bidirectional"))
    )
    (net (code "56") (name "Net-(D12A-AC)") (class "Default")
      (node (ref "D12") (pin "4") (pinfunction "AC_4") (pintype "passive"))
      (node (ref "R16") (pin "4") (pinfunction "2_4") (pintype "passive"))
      (node (ref "U3") (pin "41") (pinfunction "PB5:OC1A:PCINT5_41") (pintype "bidirectional"))
    )
    (net (code "57") (name "Net-(DIGITAL0-Pad1)") (class "Default")
      (node (ref "DIGITAL0") (pin "1") (pinfunction "1_1") (pintype "passive"))
      (node (ref "R15") (pin "1") (pinfunction "1_1") (pintype "passive"))
    )
    (net (code "58") (name "Net-(DIGITAL0-Pad5)") (class "Default")
      (node (ref "DIGITAL0") (pin "5") (pinfunction "5_5") (pintype "passive"))
      (node (ref "R14") (pin "1") (pinfunction "1_1") (pintype "passive"))
    )
    (net (code "59") (name "Net-(DIGITAL1-Pad5)") (class "Default")
      (node (ref "DIGITAL1") (pin "5") (pinfunction "5_5") (pintype "passive"))
      (node (ref "R16") (pin "1") (pinfunction "1_1") (pintype "passive"))
      (node (ref "SPI") (pin "2") (pinfunction "2_2") (pintype "passive"))
    )
    (net (code "60") (name "Net-(L-PadA)") (class "Default")
      (node (ref "L") (pin "A") (pinfunction "A_A") (pintype "passive"))
      (node (ref "R7") (pin "2") (pinfunction "2_2") (pintype "passive"))
    )
    (net (code "61") (name "Net-(PWR-LED-Pad1)") (class "Default")
      (node (ref "PWR-LED") (pin "1") (pinfunction "1_1") (pintype "passive"))
      (node (ref "R6") (pin "1") (pinfunction "1_1") (pintype "passive"))
    )
    (net (code "62") (name "Net-(PWR-PadA)") (class "Default")
      (node (ref "PWR") (pin "A") (pinfunction "A_A") (pintype "passive"))
      (node (ref "R6") (pin "2") (pinfunction "2_2") (pintype "passive"))
    )
    (net (code "63") (name "Net-(R7B-2)") (class "Default")
      (node (ref "R7") (pin "4") (pinfunction "2_4") (pintype "passive"))
      (node (ref "TX") (pin "C") (pinfunction "C_C") (pintype "passive"))
    )
    (net (code "64") (name "Net-(R7D-2)") (class "Default")
      (node (ref "R7") (pin "8") (pinfunction "2_8") (pintype "passive"))
      (node (ref "RX") (pin "C") (pinfunction "C_C") (pintype "passive"))
    )
    (net (code "65") (name "Net-(R8-Pad2)") (class "Default")
      (node (ref "R8") (pin "2") (pinfunction "2_2") (pintype "passive"))
      (node (ref "RFRX") (pin "C") (pinfunction "C_C") (pintype "passive"))
    )
    (net (code "66") (name "Net-(R9-Pad2)") (class "Default")
      (node (ref "R9") (pin "2") (pinfunction "2_2") (pintype "passive"))
      (node (ref "RFTX") (pin "C") (pinfunction "C_C") (pintype "passive"))
    )
    (net (code "67") (name "Net-(R12B-1)") (class "Default")
      (node (ref "ANALOG") (pin "2") (pinfunction "2_2") (pintype "passive"))
      (node (ref "R12") (pin "3") (pinfunction "1_3") (pintype "passive"))
    )
    (net (code "68") (name "Net-(R12C-1)") (class "Default")
      (node (ref "ANALOG") (pin "3") (pinfunction "3_3") (pintype "passive"))
      (node (ref "R12") (pin "5") (pinfunction "1_5") (pintype "passive"))
    )
    (net (code "69") (name "Net-(R12D-1)") (class "Default")
      (node (ref "ANALOG") (pin "4") (pinfunction "4_4") (pintype "passive"))
      (node (ref "R12") (pin "7") (pinfunction "1_7") (pintype "passive"))
    )
    (net (code "70") (name "Net-(R13B-1)") (class "Default")
      (node (ref "DIGITAL1") (pin "1") (pinfunction "1_1") (pintype "passive"))
      (node (ref "R13") (pin "3") (pinfunction "1_3") (pintype "passive"))
    )
    (net (code "71") (name "Net-(R13C-1)") (class "Default")
      (node (ref "DIGITAL1") (pin "2") (pinfunction "2_2") (pintype "passive"))
      (node (ref "R13") (pin "5") (pinfunction "1_5") (pintype "passive"))
    )
    (net (code "72") (name "Net-(R13D-1)") (class "Default")
      (node (ref "DIGITAL1") (pin "3") (pinfunction "3_3") (pintype "passive"))
      (node (ref "R13") (pin "7") (pinfunction "1_7") (pintype "passive"))
    )
    (net (code "73") (name "Net-(R14B-1)") (class "Default")
      (node (ref "DIGITAL0") (pin "6") (pinfunction "6_6") (pintype "passive"))
      (node (ref "R14") (pin "3") (pinfunction "1_3") (pintype "passive"))
    )
    (net (code "74") (name "Net-(R14C-1)") (class "Default")
      (node (ref "DIGITAL0") (pin "7") (pinfunction "7_7") (pintype "passive"))
      (node (ref "R14") (pin "5") (pinfunction "1_5") (pintype "passive"))
    )
    (net (code "75") (name "Net-(R14D-1)") (class "Default")
      (node (ref "DIGITAL0") (pin "8") (pinfunction "8_8") (pintype "passive"))
      (node (ref "R14") (pin "7") (pinfunction "1_7") (pintype "passive"))
    )
    (net (code "76") (name "Net-(R15B-1)") (class "Default")
      (node (ref "DIGITAL0") (pin "2") (pinfunction "2_2") (pintype "passive"))
      (node (ref "R15") (pin "3") (pinfunction "1_3") (pintype "passive"))
    )
    (net (code "77") (name "Net-(R15C-1)") (class "Default")
      (node (ref "DIGITAL0") (pin "3") (pinfunction "3_3") (pintype "passive"))
      (node (ref "R15") (pin "5") (pinfunction "1_5") (pintype "passive"))
    )
    (net (code "78") (name "Net-(R15D-1)") (class "Default")
      (node (ref "DIGITAL0") (pin "4") (pinfunction "4_4") (pintype "passive"))
      (node (ref "R15") (pin "7") (pinfunction "1_7") (pintype "passive"))
    )
    (net (code "79") (name "Net-(R16C-1)") (class "Default")
      (node (ref "DIGITAL1") (pin "6") (pinfunction "6_6") (pintype "passive"))
      (node (ref "R16") (pin "5") (pinfunction "1_5") (pintype "passive"))
      (node (ref "SPI") (pin "1") (pinfunction "1_1") (pintype "passive"))
    )
    (net (code "80") (name "Net-(R16D-1)") (class "Default")
      (node (ref "D11-J") (pin "1") (pinfunction "1_1") (pintype "passive"))
      (node (ref "R16") (pin "7") (pinfunction "1_7") (pintype "passive"))
      (node (ref "SPI") (pin "3") (pinfunction "3_3") (pintype "passive"))
    )
    (net (code "81") (name "Net-(R17B-1)") (class "Default")
      (node (ref "ANALOG") (pin "6") (pinfunction "6_6") (pintype "passive"))
      (node (ref "R17") (pin "3") (pinfunction "1_3") (pintype "passive"))
    )
    (net (code "82") (name "Net-(U3-AVDD)") (class "Default")
      (node (ref "C16") (pin "2") (pinfunction "2_2") (pintype "passive"))
      (node (ref "U3") (pin "60") (pinfunction "AVDD_60") (pintype "bidirectional"))
    )
    (net (code "83") (name "Net-(U3-CLKI)") (class "Default")
      (node (ref "CLKI") (pin "1") (pinfunction "1_1") (pintype "passive"))
      (node (ref "U3") (pin "33") (pinfunction "CLKI_33") (pintype "bidirectional"))
    )
    (net (code "84") (name "Net-(U3-PF7:ADC7:TDI)") (class "Default")
      (node (ref "AUX") (pin "11") (pinfunction "11_11") (pintype "passive"))
      (node (ref "U3") (pin "6") (pinfunction "PF7:ADC7:TDI_6") (pintype "bidirectional"))
    )
    (net (code "85") (name "Net-(U3-PG0:DIG3)") (class "Default")
      (node (ref "AUX") (pin "12") (pinfunction "12_12") (pintype "passive"))
      (node (ref "U3") (pin "14") (pinfunction "PG0:DIG3_14") (pintype "bidirectional"))
    )
    (net (code "86") (name "Net-(U3-PG1:DIG1)") (class "Default")
      (node (ref "AUX") (pin "9") (pinfunction "9_9") (pintype "passive"))
      (node (ref "U3") (pin "15") (pinfunction "PG1:DIG1_15") (pintype "bidirectional"))
    )
    (net (code "87") (name "Net-(U3-PG2:AMR)") (class "Default")
      (node (ref "AUX") (pin "10") (pinfunction "10_10") (pintype "passive"))
      (node (ref "U3") (pin "16") (pinfunction "PG2:AMR_16") (pintype "bidirectional"))
    )
    (net (code "88") (name "Net-(U3-PG3:TOSC2)") (class "Default")
      (node (ref "AUX") (pin "7") (pinfunction "7_7") (pintype "passive"))
      (node (ref "C8") (pin "2") (pinfunction "2_2") (pintype "passive"))
      (node (ref "Q2") (pin "1") (pinfunction "1_1") (pintype "passive"))
      (node (ref "U3") (pin "17") (pinfunction "PG3:TOSC2_17") (pintype "bidirectional"))
    )
    (net (code "89") (name "Net-(U3-PG4:TOSC1)") (class "Default")
      (node (ref "AUX") (pin "8") (pinfunction "8_8") (pintype "passive"))
      (node (ref "C7") (pin "2") (pinfunction "2_2") (pintype "passive"))
      (node (ref "Q2") (pin "2") (pinfunction "2_2") (pintype "passive"))
      (node (ref "U3") (pin "18") (pinfunction "PG4:TOSC1_18") (pintype "bidirectional"))
    )
    (net (code "90") (name "Net-(U3-PG5:OC0B)") (class "Default")
      (node (ref "AUX") (pin "5") (pinfunction "5_5") (pintype "passive"))
      (node (ref "U3") (pin "19") (pinfunction "PG5:OC0B_19") (pintype "bidirectional"))
    )
    (net (code "91") (name "Net-(U3-RFN)") (class "Default")
      (node (ref "C11") (pin "2") (pinfunction "2_2") (pintype "passive"))
      (node (ref "U3") (pin "9") (pinfunction "RFN_9") (pintype "bidirectional"))
    )
    (net (code "92") (name "Net-(U3-RFP)") (class "Default")
      (node (ref "C10") (pin "2") (pinfunction "2_2") (pintype "passive"))
      (node (ref "U3") (pin "8") (pinfunction "RFP_8") (pintype "bidirectional"))
    )
    (net (code "93") (name "Net-(U3-XTAL1)") (class "Default")
      (node (ref "C2") (pin "2") (pinfunction "2_2") (pintype "passive"))
      (node (ref "Q1") (pin "2") (pinfunction "2_2") (pintype "passive"))
      (node (ref "U3") (pin "56") (pinfunction "XTAL1_56") (pintype "bidirectional"))
    )
    (net (code "94") (name "Net-(U3-XTAL2)") (class "Default")
      (node (ref "C1") (pin "2") (pinfunction "2_2") (pintype "passive"))
      (node (ref "Q1") (pin "1") (pinfunction "1_1") (pintype "passive"))
      (node (ref "U3") (pin "57") (pinfunction "XTAL2_57") (pintype "bidirectional"))
    )
    (net (code "95") (name "Net-(U4-3V3OUT)") (class "Default")
      (node (ref "C17") (pin "1") (pinfunction "1_1") (pintype "passive"))
      (node (ref "U4") (pin "13") (pinfunction "3V3OUT_13") (pintype "bidirectional"))
      (node (ref "U4") (pin "14") (pinfunction "RESET#_14") (pintype "bidirectional"))
      (node (ref "U4") (pin "3") (pinfunction "VCCIO_3") (pintype "bidirectional"))
    )
    (net (code "96") (name "Net-(U4-DTR#)") (class "Default")
      (node (ref "C9") (pin "1") (pinfunction "1_1") (pintype "passive"))
      (node (ref "U4") (pin "1") (pinfunction "DTR#_1") (pintype "bidirectional"))
    )
    (net (code "97") (name "Net-(U4-USBDM)") (class "Default")
      (node (ref "R4") (pin "2") (pinfunction "2_2") (pintype "passive"))
      (node (ref "U4") (pin "12") (pinfunction "USBDM_12") (pintype "bidirectional"))
    )
    (net (code "98") (name "Net-(U4-USBDP)") (class "Default")
      (node (ref "R5") (pin "2") (pinfunction "2_2") (pintype "passive"))
      (node (ref "U4") (pin "11") (pinfunction "USBDP_11") (pintype "bidirectional"))
    )
    (net (code "99") (name "Net-(U4-VCC)") (class "Default")
      (node (ref "L1") (pin "2") (pinfunction "2_2") (pintype "passive"))
      (node (ref "U4") (pin "15") (pinfunction "VCC_15") (pintype "bidirectional"))
    )
    (net (code "100") (name "Net-(U7-PROG)") (class "Default")
      (node (ref "R2") (pin "2") (pinfunction "2_2") (pintype "passive"))
      (node (ref "U7") (pin "5") (pinfunction "PROG_5") (pintype "input"))
    )
    (net (code "101") (name "Net-(U7-STAT)") (class "Default")
      (node (ref "R3") (pin "1") (pinfunction "1_1") (pintype "passive"))
      (node (ref "U7") (pin "1") (pinfunction "STAT_1") (pintype "output"))
    )
    (net (code "102") (name "Net-(U7-VBAT)") (class "Default")
      (node (ref "BAT-TEST") (pin "TP") (pinfunction "TP_TP") (pintype "input"))
      (node (ref "C3") (pin "1") (pinfunction "1_1") (pintype "passive"))
      (node (ref "CHG") (pin "A") (pinfunction "A_A") (pintype "passive"))
      (node (ref "D14") (pin "A") (pinfunction "A_A") (pintype "passive"))
      (node (ref "JP1") (pin "2") (pinfunction "2_2") (pintype "passive"))
      (node (ref "R10") (pin "1") (pinfunction "1_1") (pintype "passive"))
      (node (ref "U7") (pin "3") (pinfunction "VBAT_3") (pintype "power_in"))
    )
    (net (code "103") (name "unconnected-(POWER-Pad1)") (class "Default")
      (node (ref "POWER") (pin "1") (pinfunction "1_1") (pintype "passive"))
    )
    (net (code "104") (name "unconnected-(U3-~{RESET_OUT}-Pad13)") (class "Default")
      (node (ref "U3") (pin "13") (pinfunction "~{RESET_OUT}_13") (pintype "bidirectional"))
    )
    (net (code "105") (name "unconnected-(U4-CBUS0-Pad18)") (class "Default")
      (node (ref "U4") (pin "18") (pinfunction "CBUS0_18") (pintype "bidirectional"))
    )
    (net (code "106") (name "unconnected-(U4-CBUS3-Pad19)") (class "Default")
      (node (ref "U4") (pin "19") (pinfunction "CBUS3_19") (pintype "bidirectional"))
    )
    (net (code "107") (name "unconnected-(U4-CTS#-Pad9)") (class "Default")
      (node (ref "U4") (pin "9") (pinfunction "CTS#_9") (pintype "bidirectional"))
    )
    (net (code "108") (name "unconnected-(U4-DCD#-Pad8)") (class "Default")
      (node (ref "U4") (pin "8") (pinfunction "DCD#_8") (pintype "bidirectional"))
    )
    (net (code "109") (name "unconnected-(U4-DSR#-Pad7)") (class "Default")
      (node (ref "U4") (pin "7") (pinfunction "DSR#_7") (pintype "bidirectional"))
    )
    (net (code "110") (name "unconnected-(U4-RI#-Pad5)") (class "Default")
      (node (ref "U4") (pin "5") (pinfunction "RI#_5") (pintype "bidirectional"))
    )
    (net (code "111") (name "unconnected-(U4-RTS#-Pad2)") (class "Default")
      (node (ref "U4") (pin "2") (pinfunction "RTS#_2") (pintype "bidirectional"))
    )
  )
)
